# Power_Rail.net
KiCad netlist of a schematic drawn in EAGLE
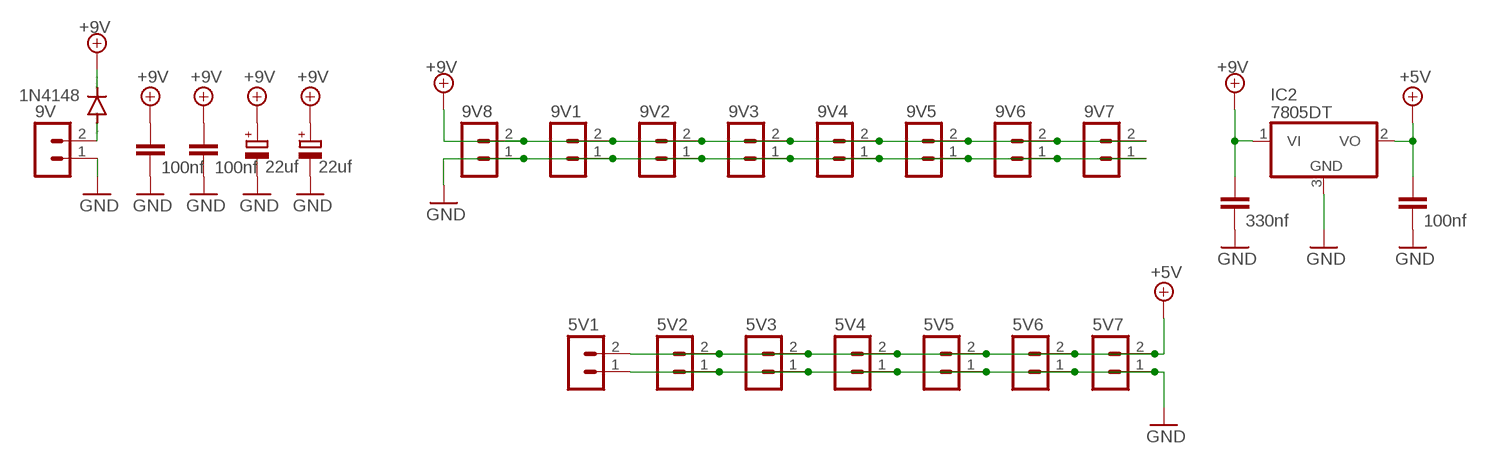
[diagram p0: schematic, sheet 1]

(export (version "E")
  (design (tool "Eeschema 10.0.6"))
  (components
    (comp (ref "5V1")
      (value "B2B-PH-K-S")
      (footprint "eagle-import:B2B-PH-K-S")
      (libsource (lib "eagle-import") (part "B2B-PH-K-S"))
    )
    (comp (ref "5V2")
      (value "B2B-PH-K-S")
      (footprint "eagle-import:B2B-PH-K-S")
      (libsource (lib "eagle-import") (part "B2B-PH-K-S"))
    )
    (comp (ref "5V3")
      (value "B2B-PH-K-S")
      (footprint "eagle-import:B2B-PH-K-S")
      (libsource (lib "eagle-import") (part "B2B-PH-K-S"))
    )
    (comp (ref "5V4")
      (value "B2B-PH-K-S")
      (footprint "eagle-import:B2B-PH-K-S")
      (libsource (lib "eagle-import") (part "B2B-PH-K-S"))
    )
    (comp (ref "5V5")
      (value "B2B-PH-K-S")
      (footprint "eagle-import:B2B-PH-K-S")
      (libsource (lib "eagle-import") (part "B2B-PH-K-S"))
    )
    (comp (ref "5V6")
      (value "B2B-PH-K-S")
      (footprint "eagle-import:B2B-PH-K-S")
      (libsource (lib "eagle-import") (part "B2B-PH-K-S"))
    )
    (comp (ref "5V7")
      (value "B2B-PH-K-S")
      (footprint "eagle-import:B2B-PH-K-S")
      (libsource (lib "eagle-import") (part "B2B-PH-K-S"))
    )
    (comp (ref "9V")
      (value "B2B-PH-K-S")
      (footprint "eagle-import:B2B-PH-K-S")
      (libsource (lib "eagle-import") (part "B2B-PH-K-S"))
    )
    (comp (ref "9V1")
      (value "B2B-PH-K-S")
      (footprint "eagle-import:B2B-PH-K-S")
      (libsource (lib "eagle-import") (part "B2B-PH-K-S"))
    )
    (comp (ref "9V2")
      (value "B2B-PH-K-S")
      (footprint "eagle-import:B2B-PH-K-S")
      (libsource (lib "eagle-import") (part "B2B-PH-K-S"))
    )
    (comp (ref "9V3")
      (value "B2B-PH-K-S")
      (footprint "eagle-import:B2B-PH-K-S")
      (libsource (lib "eagle-import") (part "B2B-PH-K-S"))
    )
    (comp (ref "9V4")
      (value "B2B-PH-K-S")
      (footprint "eagle-import:B2B-PH-K-S")
      (libsource (lib "eagle-import") (part "B2B-PH-K-S"))
    )
    (comp (ref "9V5")
      (value "B2B-PH-K-S")
      (footprint "eagle-import:B2B-PH-K-S")
      (libsource (lib "eagle-import") (part "B2B-PH-K-S"))
    )
    (comp (ref "9V6")
      (value "B2B-PH-K-S")
      (footprint "eagle-import:B2B-PH-K-S")
      (libsource (lib "eagle-import") (part "B2B-PH-K-S"))
    )
    (comp (ref "9V7")
      (value "B2B-PH-K-S")
      (footprint "eagle-import:B2B-PH-K-S")
      (libsource (lib "eagle-import") (part "B2B-PH-K-S"))
    )
    (comp (ref "9V8")
      (value "B2B-PH-K-S")
      (footprint "eagle-import:B2B-PH-K-S")
      (libsource (lib "eagle-import") (part "B2B-PH-K-S"))
    )
    (comp (ref "C1")
      (value "330nf")
      (footprint "eagle-import:C050-024X044")
      (libsource (lib "eagle-import") (part "C-EU050-024X044"))
    )
    (comp (ref "C2")
      (value "100nf")
      (footprint "eagle-import:C050-024X044")
      (libsource (lib "eagle-import") (part "C-EU050-024X044"))
    )
    (comp (ref "C3")
      (value "22uf")
      (footprint "eagle-import:E2-5")
      (libsource (lib "eagle-import") (part "CPOL-EUE2-5"))
    )
    (comp (ref "C4")
      (value "22uf")
      (footprint "eagle-import:E2-5")
      (libsource (lib "eagle-import") (part "CPOL-EUE2-5"))
    )
    (comp (ref "C5")
      (value "100nf")
      (footprint "eagle-import:C050-024X044")
      (libsource (lib "eagle-import") (part "C-EU050-024X044"))
    )
    (comp (ref "C6")
      (value "100nf")
      (footprint "eagle-import:C050-024X044")
      (libsource (lib "eagle-import") (part "C-EU050-024X044"))
    )
    (comp (ref "D2")
      (value "1N4148")
      (footprint "eagle-import:DO35-7")
      (libsource (lib "eagle-import") (part "1N4148DO35-7"))
    )
    (comp (ref "IC2")
      (value "7805DT")
      (footprint "eagle-import:TO252")
      (libsource (lib "eagle-import") (part "78DT05"))
    )
  )
  (nets
    (net (code "1") (name "+5V") (class "Default")
      (node (ref "5V1") (pin "2") (pinfunction "2_2") (pintype "passive"))
      (node (ref "5V2") (pin "2") (pinfunction "2_2") (pintype "passive"))
      (node (ref "5V3") (pin "2") (pinfunction "2_2") (pintype "passive"))
      (node (ref "5V4") (pin "2") (pinfunction "2_2") (pintype "passive"))
      (node (ref "5V5") (pin "2") (pinfunction "2_2") (pintype "passive"))
      (node (ref "5V6") (pin "2") (pinfunction "2_2") (pintype "passive"))
      (node (ref "5V7") (pin "2") (pinfunction "2_2") (pintype "passive"))
      (node (ref "C2") (pin "1") (pinfunction "1_1") (pintype "passive"))
      (node (ref "IC2") (pin "2") (pinfunction "VO_2") (pintype "passive"))
    )
    (net (code "2") (name "+9V") (class "Default")
      (node (ref "9V1") (pin "2") (pinfunction "2_2") (pintype "passive"))
      (node (ref "9V2") (pin "2") (pinfunction "2_2") (pintype "passive"))
      (node (ref "9V3") (pin "2") (pinfunction "2_2") (pintype "passive"))
      (node (ref "9V4") (pin "2") (pinfunction "2_2") (pintype "passive"))
      (node (ref "9V5") (pin "2") (pinfunction "2_2") (pintype "passive"))
      (node (ref "9V6") (pin "2") (pinfunction "2_2") (pintype "passive"))
      (node (ref "9V7") (pin "2") (pinfunction "2_2") (pintype "passive"))
      (node (ref "9V8") (pin "2") (pinfunction "2_2") (pintype "passive"))
      (node (ref "C1") (pin "1") (pinfunction "1_1") (pintype "passive"))
      (node (ref "C3") (pin "+") (pinfunction "+_+") (pintype "passive"))
      (node (ref "C4") (pin "+") (pinfunction "+_+") (pintype "passive"))
      (node (ref "C5") (pin "1") (pinfunction "1_1") (pintype "passive"))
      (node (ref "C6") (pin "1") (pinfunction "1_1") (pintype "passive"))
      (node (ref "D2") (pin "C") (pinfunction "C_C") (pintype "passive"))
      (node (ref "IC2") (pin "1") (pinfunction "VI_1") (pintype "input"))
    )
    (net (code "3") (name "GND") (class "Default")
      (node (ref "5V1") (pin "1") (pinfunction "1_1") (pintype "passive"))
      (node (ref "5V2") (pin "1") (pinfunction "1_1") (pintype "passive"))
      (node (ref "5V3") (pin "1") (pinfunction "1_1") (pintype "passive"))
      (node (ref "5V4") (pin "1") (pinfunction "1_1") (pintype "passive"))
      (node (ref "5V5") (pin "1") (pinfunction "1_1") (pintype "passive"))
      (node (ref "5V6") (pin "1") (pinfunction "1_1") (pintype "passive"))
      (node (ref "5V7") (pin "1") (pinfunction "1_1") (pintype "passive"))
      (node (ref "9V") (pin "1") (pinfunction "1_1") (pintype "passive"))
      (node (ref "9V1") (pin "1") (pinfunction "1_1") (pintype "passive"))
      (node (ref "9V2") (pin "1") (pinfunction "1_1") (pintype "passive"))
      (node (ref "9V3") (pin "1") (pinfunction "1_1") (pintype "passive"))
      (node (ref "9V4") (pin "1") (pinfunction "1_1") (pintype "passive"))
      (node (ref "9V5") (pin "1") (pinfunction "1_1") (pintype "passive"))
      (node (ref "9V6") (pin "1") (pinfunction "1_1") (pintype "passive"))
      (node (ref "9V7") (pin "1") (pinfunction "1_1") (pintype "passive"))
      (node (ref "9V8") (pin "1") (pinfunction "1_1") (pintype "passive"))
      (node (ref "C1") (pin "2") (pinfunction "2_2") (pintype "passive"))
      (node (ref "C2") (pin "2") (pinfunction "2_2") (pintype "passive"))
      (node (ref "C3") (pin "-") (pinfunction "-_-") (pintype "passive"))
      (node (ref "C4") (pin "-") (pinfunction "-_-") (pintype "passive"))
      (node (ref "C5") (pin "2") (pinfunction "2_2") (pintype "passive"))
      (node (ref "C6") (pin "2") (pinfunction "2_2") (pintype "passive"))
      (node (ref "IC2") (pin "3") (pinfunction "GND_3") (pintype "passive"))
    )
    (net (code "4") (name "Net-(9V-Pad2)") (class "Default")
      (node (ref "9V") (pin "2") (pinfunction "2_2") (pintype "passive"))
      (node (ref "D2") (pin "A") (pinfunction "A_A") (pintype "passive"))
    )
  )
)
